# four-step-octaved.net
KiCad netlist of a schematic drawn in EAGLE
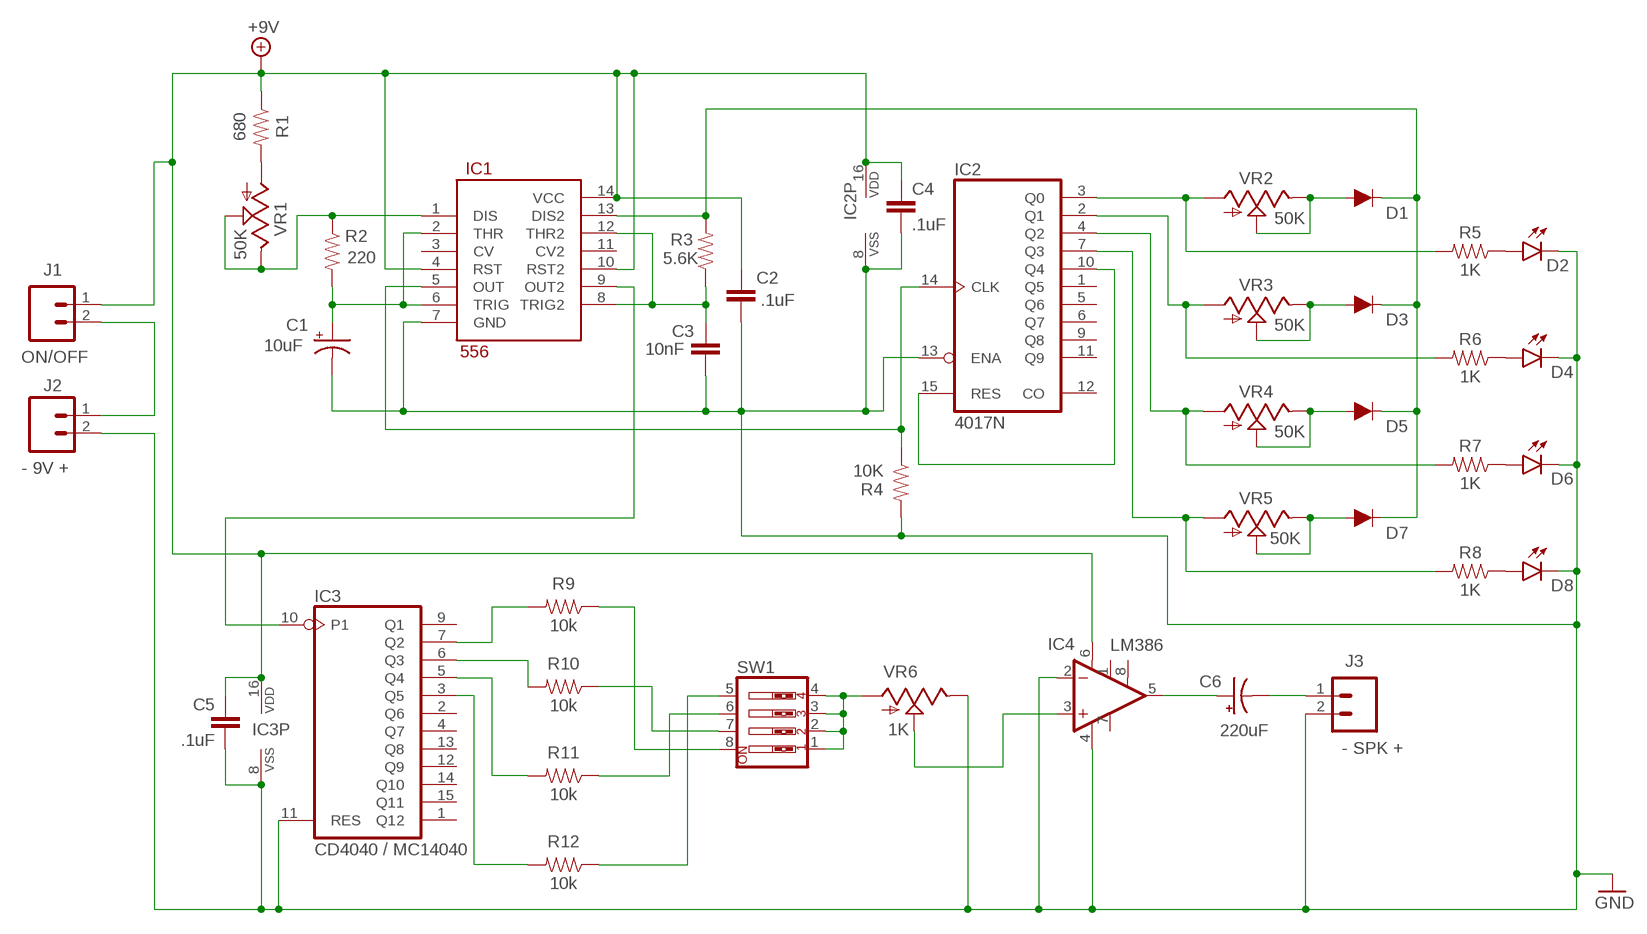
[diagram p0: schematic, sheet 1]

(export (version "E")
  (design (tool "Eeschema 10.0.6"))
  (components
    (comp (ref "C1")
      (value "10uF")
      (footprint "eagle-import:CPOL-RADIAL-2.5MM-5MM")
      (libsource (lib "eagle-import") (part "10UF-POLAR-RADIAL-2.5MM-25V-20%"))
    )
    (comp (ref "C2")
      (value ".1uF")
      (footprint "eagle-import:CAP-PTH-SMALL-KIT")
      (libsource (lib "eagle-import") (part "0.1UF-KIT-EZ-50V-20%"))
    )
    (comp (ref "C3")
      (value "10nF")
      (footprint "eagle-import:CAP-PTH-SMALL-KIT")
      (libsource (lib "eagle-import") (part "0.1UF-KIT-EZ-50V-20%"))
    )
    (comp (ref "C4")
      (value ".1uF")
      (footprint "eagle-import:CAP-PTH-SMALL-KIT")
      (libsource (lib "eagle-import") (part "0.1UF-KIT-EZ-50V-20%"))
    )
    (comp (ref "C5")
      (value ".1uF")
      (footprint "eagle-import:CAP-PTH-SMALL-KIT")
      (libsource (lib "eagle-import") (part "0.1UF-KIT-EZ-50V-20%"))
    )
    (comp (ref "C6")
      (value "220uF")
      (footprint "eagle-import:CPOL-RADIAL-2.5MM-5MM")
      (libsource (lib "eagle-import") (part "10UF-POLAR-RADIAL-2.5MM-25V-20%"))
    )
    (comp (ref "D1")
      (value "DIODE-PTH")
      (footprint "eagle-import:DIODE-1N4001")
      (libsource (lib "eagle-import") (part "DIODE-PTH"))
    )
    (comp (ref "D2")
      (value "LED3MM")
      (footprint "eagle-import:LED_3MM")
      (libsource (lib "eagle-import") (part "LED3MM"))
    )
    (comp (ref "D3")
      (value "DIODE-PTH")
      (footprint "eagle-import:DIODE-1N4001")
      (libsource (lib "eagle-import") (part "DIODE-PTH"))
    )
    (comp (ref "D4")
      (value "LED3MM")
      (footprint "eagle-import:LED_3MM")
      (libsource (lib "eagle-import") (part "LED3MM"))
    )
    (comp (ref "D5")
      (value "DIODE-PTH")
      (footprint "eagle-import:DIODE-1N4001")
      (libsource (lib "eagle-import") (part "DIODE-PTH"))
    )
    (comp (ref "D6")
      (value "LED3MM")
      (footprint "eagle-import:LED_3MM")
      (libsource (lib "eagle-import") (part "LED3MM"))
    )
    (comp (ref "D7")
      (value "DIODE-PTH")
      (footprint "eagle-import:DIODE-1N4001")
      (libsource (lib "eagle-import") (part "DIODE-PTH"))
    )
    (comp (ref "D8")
      (value "LED3MM")
      (footprint "eagle-import:LED_3MM")
      (libsource (lib "eagle-import") (part "LED3MM"))
    )
    (comp (ref "IC1")
      (value "556")
      (footprint "eagle-import:DIP14")
      (libsource (lib "eagle-import") (part "556"))
    )
    (comp (ref "IC2")
      (value "4017N")
      (footprint "eagle-import:DIL16")
      (libsource (lib "eagle-import") (part "4017N"))
    )
    (comp (ref "IC3")
      (value "CD4040 / MC14040")
      (footprint "eagle-import:DIL16")
      (libsource (lib "eagle-import") (part "4040N"))
    )
    (comp (ref "IC4")
      (value "LM386")
      (footprint "eagle-import:DIP08")
      (libsource (lib "eagle-import") (part "LM386"))
    )
    (comp (ref "J1")
      (value "ON/OFF")
      (footprint "eagle-import:1X02")
      (libsource (lib "eagle-import") (part "CONN_02"))
    )
    (comp (ref "J2")
      (value "- 9V +")
      (footprint "eagle-import:1X02")
      (libsource (lib "eagle-import") (part "CONN_02"))
    )
    (comp (ref "J3")
      (value "- SPK +")
      (footprint "eagle-import:1X02")
      (libsource (lib "eagle-import") (part "CONN_02"))
    )
    (comp (ref "R1")
      (value "680")
      (footprint "eagle-import:AXIAL-0.3")
      (libsource (lib "eagle-import") (part "1KOHM-HORIZ-1/4W-1%"))
    )
    (comp (ref "R2")
      (value "220")
      (footprint "eagle-import:AXIAL-0.3")
      (libsource (lib "eagle-import") (part "1KOHM-HORIZ-1/4W-1%"))
    )
    (comp (ref "R3")
      (value "5.6K")
      (footprint "eagle-import:AXIAL-0.3")
      (libsource (lib "eagle-import") (part "1KOHM-HORIZ-1/4W-1%"))
    )
    (comp (ref "R4")
      (value "10K")
      (footprint "eagle-import:AXIAL-0.3")
      (libsource (lib "eagle-import") (part "1KOHM-HORIZ-1/4W-1%"))
    )
    (comp (ref "R5")
      (value "1K")
      (footprint "eagle-import:AXIAL-0.3")
      (libsource (lib "eagle-import") (part "1KOHM-HORIZ-1/4W-1%"))
    )
    (comp (ref "R6")
      (value "1K")
      (footprint "eagle-import:AXIAL-0.3")
      (libsource (lib "eagle-import") (part "1KOHM-HORIZ-1/4W-1%"))
    )
    (comp (ref "R7")
      (value "1K")
      (footprint "eagle-import:AXIAL-0.3")
      (libsource (lib "eagle-import") (part "1KOHM-HORIZ-1/4W-1%"))
    )
    (comp (ref "R8")
      (value "1K")
      (footprint "eagle-import:AXIAL-0.3")
      (libsource (lib "eagle-import") (part "1KOHM-HORIZ-1/4W-1%"))
    )
    (comp (ref "R9")
      (value "10k")
      (footprint "eagle-import:AXIAL-0.3")
      (libsource (lib "eagle-import") (part "1KOHM-HORIZ-1/4W-1%"))
    )
    (comp (ref "R10")
      (value "10k")
      (footprint "eagle-import:AXIAL-0.3")
      (libsource (lib "eagle-import") (part "1KOHM-HORIZ-1/4W-1%"))
    )
    (comp (ref "R11")
      (value "10k")
      (footprint "eagle-import:AXIAL-0.3")
      (libsource (lib "eagle-import") (part "1KOHM-HORIZ-1/4W-1%"))
    )
    (comp (ref "R12")
      (value "10k")
      (footprint "eagle-import:AXIAL-0.3")
      (libsource (lib "eagle-import") (part "1KOHM-HORIZ-1/4W-1%"))
    )
    (comp (ref "SW1")
      (value "SW_DIP-4")
      (footprint "eagle-import:EDG-04")
      (libsource (lib "eagle-import") (part "SW_DIP-4"))
    )
    (comp (ref "VR1")
      (value "50K")
      (footprint "eagle-import:TRIM_POT")
      (libsource (lib "eagle-import") (part "POTTRIM"))
    )
    (comp (ref "VR2")
      (value "50K")
      (footprint "eagle-import:TRIM_POT")
      (libsource (lib "eagle-import") (part "POTTRIM"))
    )
    (comp (ref "VR3")
      (value "50K")
      (footprint "eagle-import:TRIM_POT")
      (libsource (lib "eagle-import") (part "POTTRIM"))
    )
    (comp (ref "VR4")
      (value "50K")
      (footprint "eagle-import:TRIM_POT")
      (libsource (lib "eagle-import") (part "POTTRIM"))
    )
    (comp (ref "VR5")
      (value "50K")
      (footprint "eagle-import:TRIM_POT")
      (libsource (lib "eagle-import") (part "POTTRIM"))
    )
    (comp (ref "VR6")
      (value "1K")
      (footprint "eagle-import:TRIM_POT")
      (libsource (lib "eagle-import") (part "POTTRIM"))
    )
  )
  (nets
    (net (code "1") (name "+9V") (class "Default")
      (node (ref "C2") (pin "1") (pinfunction "1_1") (pintype "passive"))
      (node (ref "C4") (pin "1") (pinfunction "1_1") (pintype "passive"))
      (node (ref "C5") (pin "1") (pinfunction "1_1") (pintype "passive"))
      (node (ref "IC1") (pin "10") (pinfunction "RST2_10") (pintype "bidirectional"))
      (node (ref "IC1") (pin "14") (pinfunction "VCC_14") (pintype "bidirectional"))
      (node (ref "IC1") (pin "4") (pinfunction "RST_4") (pintype "bidirectional"))
      (node (ref "IC2") (pin "16") (pinfunction "VDD_16") (pintype "power_in"))
      (node (ref "IC3") (pin "16") (pinfunction "VDD_16") (pintype "power_in"))
      (node (ref "IC4") (pin "6") (pinfunction "V+_6") (pintype "power_in"))
      (node (ref "J1") (pin "1") (pinfunction "1_1") (pintype "passive"))
      (node (ref "R1") (pin "P$1") (pinfunction "1_P$1") (pintype "passive"))
    )
    (net (code "2") (name "GND") (class "Default")
      (node (ref "C1") (pin "2") (pinfunction "-_2") (pintype "passive"))
      (node (ref "C2") (pin "2") (pinfunction "2_2") (pintype "passive"))
      (node (ref "C3") (pin "2") (pinfunction "2_2") (pintype "passive"))
      (node (ref "C4") (pin "2") (pinfunction "2_2") (pintype "passive"))
      (node (ref "C5") (pin "2") (pinfunction "2_2") (pintype "passive"))
      (node (ref "D2") (pin "K") (pinfunction "C_K") (pintype "passive"))
      (node (ref "D4") (pin "K") (pinfunction "C_K") (pintype "passive"))
      (node (ref "D6") (pin "K") (pinfunction "C_K") (pintype "passive"))
      (node (ref "D8") (pin "K") (pinfunction "C_K") (pintype "passive"))
      (node (ref "IC1") (pin "7") (pinfunction "GND_7") (pintype "bidirectional"))
      (node (ref "IC2") (pin "13") (pinfunction "ENA_13") (pintype "input"))
      (node (ref "IC2") (pin "8") (pinfunction "VSS_8") (pintype "power_in"))
      (node (ref "IC3") (pin "11") (pinfunction "RES_11") (pintype "input"))
      (node (ref "IC3") (pin "8") (pinfunction "VSS_8") (pintype "power_in"))
      (node (ref "IC4") (pin "2") (pinfunction "-IN_2") (pintype "input"))
      (node (ref "IC4") (pin "4") (pinfunction "V-_4") (pintype "power_in"))
      (node (ref "J2") (pin "2") (pinfunction "2_2") (pintype "passive"))
      (node (ref "J3") (pin "2") (pinfunction "2_2") (pintype "passive"))
      (node (ref "R4") (pin "P$2") (pinfunction "2_P$2") (pintype "passive"))
      (node (ref "VR6") (pin "2") (pinfunction "E_2") (pintype "passive"))
    )
    (net (code "3") (name "Net-(C1-+)") (class "Default")
      (node (ref "C1") (pin "1") (pinfunction "+_1") (pintype "passive"))
      (node (ref "IC1") (pin "2") (pinfunction "THR_2") (pintype "bidirectional"))
      (node (ref "IC1") (pin "6") (pinfunction "TRIG_6") (pintype "bidirectional"))
      (node (ref "R2") (pin "P$2") (pinfunction "2_P$2") (pintype "passive"))
    )
    (net (code "4") (name "Net-(C6-+)") (class "Default")
      (node (ref "C6") (pin "1") (pinfunction "+_1") (pintype "passive"))
      (node (ref "IC4") (pin "5") (pinfunction "OUT_5") (pintype "output"))
    )
    (net (code "5") (name "Net-(C6--)") (class "Default")
      (node (ref "C6") (pin "2") (pinfunction "-_2") (pintype "passive"))
      (node (ref "J3") (pin "1") (pinfunction "1_1") (pintype "passive"))
    )
    (net (code "6") (name "Net-(IC1-DIS)") (class "Default")
      (node (ref "IC1") (pin "1") (pinfunction "DIS_1") (pintype "bidirectional"))
      (node (ref "R2") (pin "P$1") (pinfunction "1_P$1") (pintype "passive"))
      (node (ref "VR1") (pin "1") (pinfunction "S_1") (pintype "passive"))
      (node (ref "VR1") (pin "2") (pinfunction "E_2") (pintype "passive"))
    )
    (net (code "7") (name "Net-(IC1-DIS2)") (class "Default")
      (node (ref "D1") (pin "C") (pinfunction "C_C") (pintype "passive"))
      (node (ref "D3") (pin "C") (pinfunction "C_C") (pintype "passive"))
      (node (ref "D5") (pin "C") (pinfunction "C_C") (pintype "passive"))
      (node (ref "D7") (pin "C") (pinfunction "C_C") (pintype "passive"))
      (node (ref "IC1") (pin "13") (pinfunction "DIS2_13") (pintype "bidirectional"))
      (node (ref "R3") (pin "P$2") (pinfunction "2_P$2") (pintype "passive"))
    )
    (net (code "8") (name "Net-(IC1-OUT)") (class "Default")
      (node (ref "IC1") (pin "5") (pinfunction "OUT_5") (pintype "bidirectional"))
      (node (ref "IC2") (pin "14") (pinfunction "CLK_14") (pintype "input"))
      (node (ref "R4") (pin "P$1") (pinfunction "1_P$1") (pintype "passive"))
    )
    (net (code "9") (name "Net-(IC1-OUT2)") (class "Default")
      (node (ref "IC1") (pin "9") (pinfunction "OUT2_9") (pintype "bidirectional"))
      (node (ref "IC3") (pin "10") (pinfunction "P1_10") (pintype "input"))
    )
    (net (code "10") (name "Net-(IC1-THR2)") (class "Default")
      (node (ref "C3") (pin "1") (pinfunction "1_1") (pintype "passive"))
      (node (ref "IC1") (pin "12") (pinfunction "THR2_12") (pintype "bidirectional"))
      (node (ref "IC1") (pin "8") (pinfunction "TRIG2_8") (pintype "bidirectional"))
      (node (ref "R3") (pin "P$1") (pinfunction "1_P$1") (pintype "passive"))
    )
    (net (code "11") (name "Net-(IC2A-Q0)") (class "Default")
      (node (ref "IC2") (pin "3") (pinfunction "Q0_3") (pintype "output"))
      (node (ref "R5") (pin "P$2") (pinfunction "2_P$2") (pintype "passive"))
      (node (ref "VR2") (pin "3") (pinfunction "A_3") (pintype "passive"))
    )
    (net (code "12") (name "Net-(IC2A-Q1)") (class "Default")
      (node (ref "IC2") (pin "2") (pinfunction "Q1_2") (pintype "output"))
      (node (ref "R6") (pin "P$2") (pinfunction "2_P$2") (pintype "passive"))
      (node (ref "VR3") (pin "3") (pinfunction "A_3") (pintype "passive"))
    )
    (net (code "13") (name "Net-(IC2A-Q2)") (class "Default")
      (node (ref "IC2") (pin "4") (pinfunction "Q2_4") (pintype "output"))
      (node (ref "R7") (pin "P$2") (pinfunction "2_P$2") (pintype "passive"))
      (node (ref "VR4") (pin "3") (pinfunction "A_3") (pintype "passive"))
    )
    (net (code "14") (name "Net-(IC2A-Q3)") (class "Default")
      (node (ref "IC2") (pin "7") (pinfunction "Q3_7") (pintype "output"))
      (node (ref "R8") (pin "P$2") (pinfunction "2_P$2") (pintype "passive"))
      (node (ref "VR5") (pin "3") (pinfunction "A_3") (pintype "passive"))
    )
    (net (code "15") (name "Net-(IC2A-Q4)") (class "Default")
      (node (ref "IC2") (pin "10") (pinfunction "Q4_10") (pintype "output"))
      (node (ref "IC2") (pin "15") (pinfunction "RES_15") (pintype "input"))
    )
    (net (code "16") (name "Net-(IC3A-Q2)") (class "Default")
      (node (ref "IC3") (pin "7") (pinfunction "Q2_7") (pintype "output"))
      (node (ref "R9") (pin "P$2") (pinfunction "2_P$2") (pintype "passive"))
    )
    (net (code "17") (name "Net-(IC3A-Q3)") (class "Default")
      (node (ref "IC3") (pin "6") (pinfunction "Q3_6") (pintype "output"))
      (node (ref "R10") (pin "P$2") (pinfunction "2_P$2") (pintype "passive"))
    )
    (net (code "18") (name "Net-(IC3A-Q4)") (class "Default")
      (node (ref "IC3") (pin "5") (pinfunction "Q4_5") (pintype "output"))
      (node (ref "R11") (pin "P$2") (pinfunction "2_P$2") (pintype "passive"))
    )
    (net (code "19") (name "Net-(IC3A-Q5)") (class "Default")
      (node (ref "IC3") (pin "3") (pinfunction "Q5_3") (pintype "output"))
      (node (ref "R12") (pin "P$2") (pinfunction "2_P$2") (pintype "passive"))
    )
    (net (code "20") (name "Net-(IC4-+IN)") (class "Default")
      (node (ref "IC4") (pin "3") (pinfunction "+IN_3") (pintype "input"))
      (node (ref "VR6") (pin "1") (pinfunction "S_1") (pintype "passive"))
    )
    (net (code "21") (name "Net-(J1-Pad2)") (class "Default")
      (node (ref "J1") (pin "2") (pinfunction "2_2") (pintype "passive"))
      (node (ref "J2") (pin "1") (pinfunction "1_1") (pintype "passive"))
    )
    (net (code "22") (name "Net-(R1-2)") (class "Default")
      (node (ref "R1") (pin "P$2") (pinfunction "2_P$2") (pintype "passive"))
      (node (ref "VR1") (pin "3") (pinfunction "A_3") (pintype "passive"))
    )
    (net (code "23") (name "Net-(R5-1)") (class "Default")
      (node (ref "D2") (pin "A") (pinfunction "A_A") (pintype "passive"))
      (node (ref "R5") (pin "P$1") (pinfunction "1_P$1") (pintype "passive"))
    )
    (net (code "24") (name "Net-(R6-1)") (class "Default")
      (node (ref "D4") (pin "A") (pinfunction "A_A") (pintype "passive"))
      (node (ref "R6") (pin "P$1") (pinfunction "1_P$1") (pintype "passive"))
    )
    (net (code "25") (name "Net-(R7-1)") (class "Default")
      (node (ref "D6") (pin "A") (pinfunction "A_A") (pintype "passive"))
      (node (ref "R7") (pin "P$1") (pinfunction "1_P$1") (pintype "passive"))
    )
    (net (code "26") (name "Net-(R8-1)") (class "Default")
      (node (ref "D8") (pin "A") (pinfunction "A_A") (pintype "passive"))
      (node (ref "R8") (pin "P$1") (pinfunction "1_P$1") (pintype "passive"))
    )
    (net (code "27") (name "Net-(R9-1)") (class "Default")
      (node (ref "R9") (pin "P$1") (pinfunction "1_P$1") (pintype "passive"))
      (node (ref "SW1") (pin "8") (pinfunction "8_8") (pintype "passive"))
    )
    (net (code "28") (name "Net-(R10-1)") (class "Default")
      (node (ref "R10") (pin "P$1") (pinfunction "1_P$1") (pintype "passive"))
      (node (ref "SW1") (pin "7") (pinfunction "7_7") (pintype "passive"))
    )
    (net (code "29") (name "Net-(R11-1)") (class "Default")
      (node (ref "R11") (pin "P$1") (pinfunction "1_P$1") (pintype "passive"))
      (node (ref "SW1") (pin "6") (pinfunction "6_6") (pintype "passive"))
    )
    (net (code "30") (name "Net-(R12-1)") (class "Default")
      (node (ref "R12") (pin "P$1") (pinfunction "1_P$1") (pintype "passive"))
      (node (ref "SW1") (pin "5") (pinfunction "5_5") (pintype "passive"))
    )
    (net (code "31") (name "Net-(VR2-E)") (class "Default")
      (node (ref "D1") (pin "A") (pinfunction "A_A") (pintype "passive"))
      (node (ref "VR2") (pin "1") (pinfunction "S_1") (pintype "passive"))
      (node (ref "VR2") (pin "2") (pinfunction "E_2") (pintype "passive"))
    )
    (net (code "32") (name "Net-(VR3-E)") (class "Default")
      (node (ref "D3") (pin "A") (pinfunction "A_A") (pintype "passive"))
      (node (ref "VR3") (pin "1") (pinfunction "S_1") (pintype "passive"))
      (node (ref "VR3") (pin "2") (pinfunction "E_2") (pintype "passive"))
    )
    (net (code "33") (name "Net-(VR4-E)") (class "Default")
      (node (ref "D5") (pin "A") (pinfunction "A_A") (pintype "passive"))
      (node (ref "VR4") (pin "1") (pinfunction "S_1") (pintype "passive"))
      (node (ref "VR4") (pin "2") (pinfunction "E_2") (pintype "passive"))
    )
    (net (code "34") (name "Net-(VR5-E)") (class "Default")
      (node (ref "D7") (pin "A") (pinfunction "A_A") (pintype "passive"))
      (node (ref "VR5") (pin "1") (pinfunction "S_1") (pintype "passive"))
      (node (ref "VR5") (pin "2") (pinfunction "E_2") (pintype "passive"))
    )
    (net (code "35") (name "Net-(VR6-A)") (class "Default")
      (node (ref "SW1") (pin "1") (pinfunction "1_1") (pintype "passive"))
      (node (ref "SW1") (pin "2") (pinfunction "2_2") (pintype "passive"))
      (node (ref "SW1") (pin "3") (pinfunction "3_3") (pintype "passive"))
      (node (ref "SW1") (pin "4") (pinfunction "4_4") (pintype "passive"))
      (node (ref "VR6") (pin "3") (pinfunction "A_3") (pintype "passive"))
    )
    (net (code "36") (name "unconnected-(IC1-CV-Pad3)") (class "Default")
      (node (ref "IC1") (pin "3") (pinfunction "CV_3") (pintype "bidirectional"))
    )
    (net (code "37") (name "unconnected-(IC1-CV2-Pad11)") (class "Default")
      (node (ref "IC1") (pin "11") (pinfunction "CV2_11") (pintype "bidirectional"))
    )
    (net (code "38") (name "unconnected-(IC2A-CO-Pad12)") (class "Default")
      (node (ref "IC2") (pin "12") (pinfunction "CO_12") (pintype "output"))
    )
    (net (code "39") (name "unconnected-(IC2A-Q5-Pad1)") (class "Default")
      (node (ref "IC2") (pin "1") (pinfunction "Q5_1") (pintype "output"))
    )
    (net (code "40") (name "unconnected-(IC2A-Q6-Pad5)") (class "Default")
      (node (ref "IC2") (pin "5") (pinfunction "Q6_5") (pintype "output"))
    )
    (net (code "41") (name "unconnected-(IC2A-Q7-Pad6)") (class "Default")
      (node (ref "IC2") (pin "6") (pinfunction "Q7_6") (pintype "output"))
    )
    (net (code "42") (name "unconnected-(IC2A-Q8-Pad9)") (class "Default")
      (node (ref "IC2") (pin "9") (pinfunction "Q8_9") (pintype "output"))
    )
    (net (code "43") (name "unconnected-(IC2A-Q9-Pad11)") (class "Default")
      (node (ref "IC2") (pin "11") (pinfunction "Q9_11") (pintype "output"))
    )
    (net (code "44") (name "unconnected-(IC3A-Q1-Pad9)") (class "Default")
      (node (ref "IC3") (pin "9") (pinfunction "Q1_9") (pintype "output"))
    )
    (net (code "45") (name "unconnected-(IC3A-Q6-Pad2)") (class "Default")
      (node (ref "IC3") (pin "2") (pinfunction "Q6_2") (pintype "output"))
    )
    (net (code "46") (name "unconnected-(IC3A-Q7-Pad4)") (class "Default")
      (node (ref "IC3") (pin "4") (pinfunction "Q7_4") (pintype "output"))
    )
    (net (code "47") (name "unconnected-(IC3A-Q8-Pad13)") (class "Default")
      (node (ref "IC3") (pin "13") (pinfunction "Q8_13") (pintype "output"))
    )
    (net (code "48") (name "unconnected-(IC3A-Q9-Pad12)") (class "Default")
      (node (ref "IC3") (pin "12") (pinfunction "Q9_12") (pintype "output"))
    )
    (net (code "49") (name "unconnected-(IC3A-Q10-Pad14)") (class "Default")
      (node (ref "IC3") (pin "14") (pinfunction "Q10_14") (pintype "output"))
    )
    (net (code "50") (name "unconnected-(IC3A-Q11-Pad15)") (class "Default")
      (node (ref "IC3") (pin "15") (pinfunction "Q11_15") (pintype "output"))
    )
    (net (code "51") (name "unconnected-(IC3A-Q12-Pad1)") (class "Default")
      (node (ref "IC3") (pin "1") (pinfunction "Q12_1") (pintype "output"))
    )
    (net (code "52") (name "unconnected-(IC4-BP-Pad7)") (class "Default")
      (node (ref "IC4") (pin "7") (pinfunction "BP_7") (pintype "bidirectional"))
    )
    (net (code "53") (name "unconnected-(IC4-GAIN-Pad1)") (class "Default")
      (node (ref "IC4") (pin "1") (pinfunction "GAIN_1") (pintype "bidirectional"))
    )
    (net (code "54") (name "unconnected-(IC4-GAIN-Pad8)") (class "Default")
      (node (ref "IC4") (pin "8") (pinfunction "GAIN_8") (pintype "bidirectional"))
    )
  )
)
